# TopLevel.net
KiCad netlist of a schematic drawn in Altium Designer
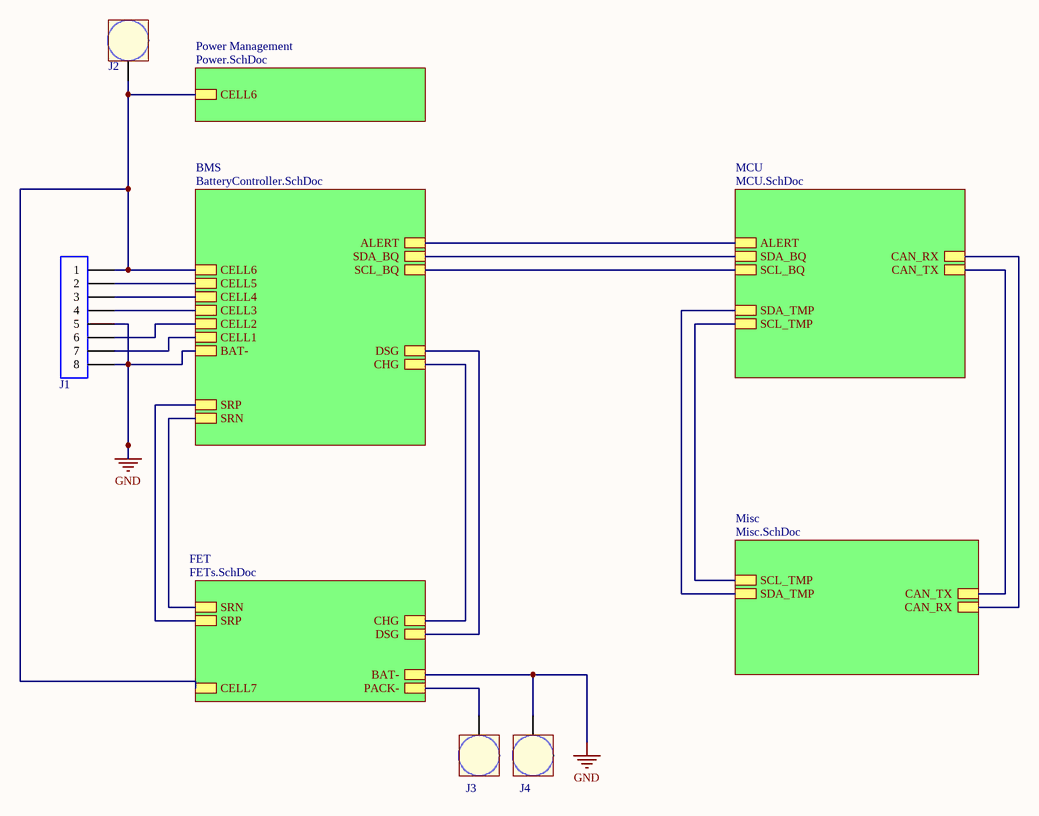
[diagram p0: TopLevel.SchDoc]

(export (version "E")
  (design (tool "Eeschema 10.0.6"))
  (components
    (comp (ref "J1")
      (value "HEADER-MALE-SMT-90C-4COL-2ROW")
      (footprint "0430450810")
      (description "Connector")
      (libsource (lib "Kaptanyums Lib") (part "0430450810"))
    )
    (comp (ref "J2")
      (value "7460305")
      (footprint "7460305")
      (description "Connector")
      (libsource (lib "") (part "7460305_1"))
    )
    (comp (ref "J3")
      (value "7460305")
      (footprint "7460305")
      (description "Connector")
      (libsource (lib "Kaptanyums Lib") (part "7460305"))
    )
    (comp (ref "J4")
      (value "7460305")
      (footprint "7460305")
      (description "Connector")
      (libsource (lib "Kaptanyums Lib") (part "7460305"))
    )
  )
  (nets
    (net (code "4") (name "/CELL1") (class "Default")
      (node (ref "J1") (pin "7") (pinfunction "7_7") (pintype "passive"))
    )
    (net (code "5") (name "/CELL2") (class "Default")
      (node (ref "J1") (pin "6") (pinfunction "6_6") (pintype "passive"))
    )
    (net (code "6") (name "/CELL3") (class "Default")
      (node (ref "J1") (pin "4") (pinfunction "4_4") (pintype "passive"))
    )
    (net (code "7") (name "/CELL4") (class "Default")
      (node (ref "J1") (pin "3") (pinfunction "3_3") (pintype "passive"))
    )
    (net (code "8") (name "/CELL5") (class "Default")
      (node (ref "J1") (pin "2") (pinfunction "2_2") (pintype "passive"))
    )
    (net (code "9") (name "/CELL6") (class "Default")
      (node (ref "J1") (pin "1") (pinfunction "1_1") (pintype "passive"))
      (node (ref "J2") (pin "1") (pinfunction "1_1") (pintype "passive"))
    )
    (net (code "12") (name "/PACK-") (class "Default")
      (node (ref "J3") (pin "1") (pinfunction "1_1") (pintype "passive"))
    )
    (net (code "19") (name "GND") (class "Default")
      (node (ref "J1") (pin "5") (pinfunction "5_5") (pintype "passive"))
      (node (ref "J1") (pin "8") (pinfunction "8_8") (pintype "passive"))
      (node (ref "J4") (pin "1") (pinfunction "1_1") (pintype "passive"))
    )
  )
)
